# snes_visualization_combi.net
KiCad netlist of a schematic drawn in EAGLE
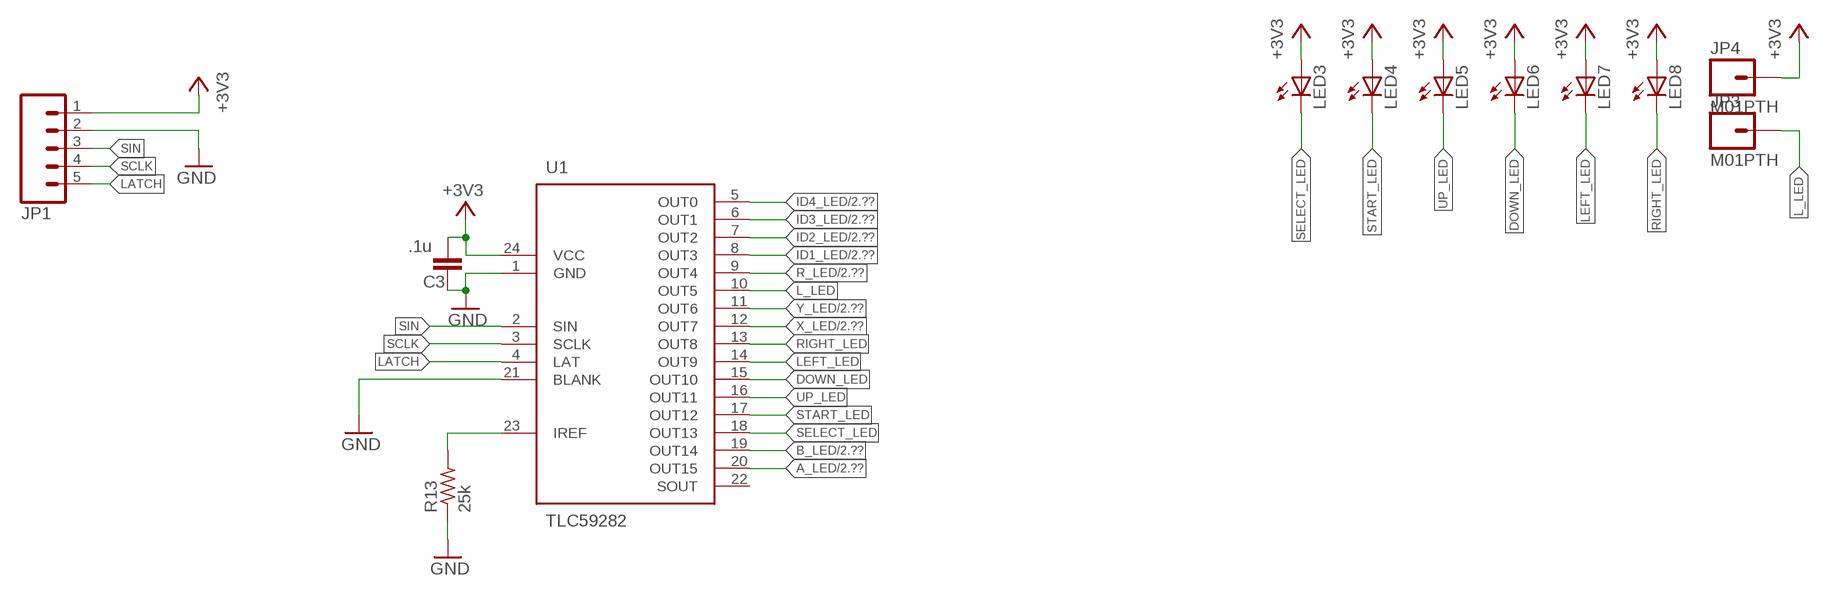
[diagram p0: schematic, sheet 1]
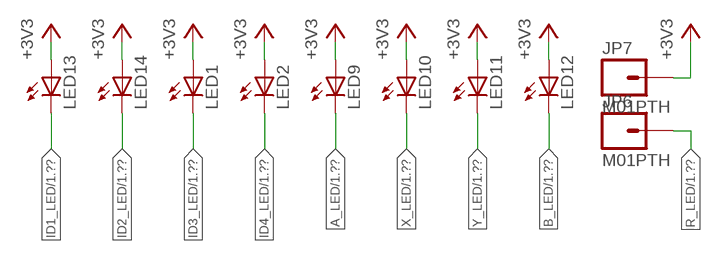
[diagram p1: schematic, sheet 2]

(export (version "E")
  (design (tool "Eeschema 10.0.6"))
  (components
    (comp (ref "JP6")
      (value "M01PTH")
      (footprint "eagle-import:1X01")
      (libsource (lib "eagle-import") (part "M01PTH"))
    )
    (comp (ref "JP7")
      (value "M01PTH")
      (footprint "eagle-import:1X01")
      (libsource (lib "eagle-import") (part "M01PTH"))
    )
    (comp (ref "LED1")
      (value "LED5MM")
      (footprint "eagle-import:LED5MM")
      (libsource (lib "eagle-import") (part "LED5MM"))
    )
    (comp (ref "LED2")
      (value "LED5MM")
      (footprint "eagle-import:LED5MM")
      (libsource (lib "eagle-import") (part "LED5MM"))
    )
    (comp (ref "LED9")
      (value "LED5MM")
      (footprint "eagle-import:LED5MM")
      (libsource (lib "eagle-import") (part "LED5MM"))
    )
    (comp (ref "LED10")
      (value "LED5MM")
      (footprint "eagle-import:LED5MM")
      (libsource (lib "eagle-import") (part "LED5MM"))
    )
    (comp (ref "LED11")
      (value "LED5MM")
      (footprint "eagle-import:LED5MM")
      (libsource (lib "eagle-import") (part "LED5MM"))
    )
    (comp (ref "LED12")
      (value "LED5MM")
      (footprint "eagle-import:LED5MM")
      (libsource (lib "eagle-import") (part "LED5MM"))
    )
    (comp (ref "LED13")
      (value "LED5MM")
      (footprint "eagle-import:LED5MM")
      (libsource (lib "eagle-import") (part "LED5MM"))
    )
    (comp (ref "LED14")
      (value "LED5MM")
      (footprint "eagle-import:LED5MM")
      (libsource (lib "eagle-import") (part "LED5MM"))
    )
    (comp (ref "C3")
      (value ".1u")
      (footprint "eagle-import:C0603")
      (libsource (lib "eagle-import") (part "C-EUC0603"))
    )
    (comp (ref "JP1")
      (value "M05PTH")
      (footprint "eagle-import:1X05")
      (libsource (lib "eagle-import") (part "M05PTH"))
    )
    (comp (ref "JP3")
      (value "M01PTH")
      (footprint "eagle-import:1X01")
      (libsource (lib "eagle-import") (part "M01PTH"))
    )
    (comp (ref "JP4")
      (value "M01PTH")
      (footprint "eagle-import:1X01")
      (libsource (lib "eagle-import") (part "M01PTH"))
    )
    (comp (ref "LED3")
      (value "LED3MM")
      (footprint "eagle-import:LED3MM")
      (libsource (lib "eagle-import") (part "LED3MM"))
    )
    (comp (ref "LED4")
      (value "LED3MM")
      (footprint "eagle-import:LED3MM")
      (libsource (lib "eagle-import") (part "LED3MM"))
    )
    (comp (ref "LED5")
      (value "LED5MM")
      (footprint "eagle-import:LED5MM")
      (libsource (lib "eagle-import") (part "LED5MM"))
    )
    (comp (ref "LED6")
      (value "LED5MM")
      (footprint "eagle-import:LED5MM")
      (libsource (lib "eagle-import") (part "LED5MM"))
    )
    (comp (ref "LED7")
      (value "LED5MM")
      (footprint "eagle-import:LED5MM")
      (libsource (lib "eagle-import") (part "LED5MM"))
    )
    (comp (ref "LED8")
      (value "LED5MM")
      (footprint "eagle-import:LED5MM")
      (libsource (lib "eagle-import") (part "LED5MM"))
    )
    (comp (ref "R13")
      (value "25k")
      (footprint "eagle-import:R0805")
      (libsource (lib "eagle-import") (part "R-US_R0805"))
    )
    (comp (ref "U1")
      (value "TLC59282")
      (footprint "eagle-import:R-PDSO-G24")
      (libsource (lib "eagle-import") (part "TLC59282"))
    )
  )
  (nets
    (net (code "1") (name "+3V3") (class "Default")
      (node (ref "C3") (pin "1") (pinfunction "1_1") (pintype "passive"))
      (node (ref "JP1") (pin "1") (pinfunction "1_1") (pintype "passive"))
      (node (ref "JP4") (pin "1") (pinfunction "1_1") (pintype "passive"))
      (node (ref "JP7") (pin "1") (pinfunction "1_1") (pintype "passive"))
      (node (ref "LED1") (pin "A") (pinfunction "A_A") (pintype "passive"))
      (node (ref "LED10") (pin "A") (pinfunction "A_A") (pintype "passive"))
      (node (ref "LED11") (pin "A") (pinfunction "A_A") (pintype "passive"))
      (node (ref "LED12") (pin "A") (pinfunction "A_A") (pintype "passive"))
      (node (ref "LED13") (pin "A") (pinfunction "A_A") (pintype "passive"))
      (node (ref "LED14") (pin "A") (pinfunction "A_A") (pintype "passive"))
      (node (ref "LED2") (pin "A") (pinfunction "A_A") (pintype "passive"))
      (node (ref "LED3") (pin "A") (pinfunction "A_A") (pintype "passive"))
      (node (ref "LED4") (pin "A") (pinfunction "A_A") (pintype "passive"))
      (node (ref "LED5") (pin "A") (pinfunction "A_A") (pintype "passive"))
      (node (ref "LED6") (pin "A") (pinfunction "A_A") (pintype "passive"))
      (node (ref "LED7") (pin "A") (pinfunction "A_A") (pintype "passive"))
      (node (ref "LED8") (pin "A") (pinfunction "A_A") (pintype "passive"))
      (node (ref "LED9") (pin "A") (pinfunction "A_A") (pintype "passive"))
      (node (ref "U1") (pin "24") (pinfunction "VCC_24") (pintype "input"))
    )
    (net (code "2") (name "A_LED") (class "Default")
      (node (ref "LED9") (pin "K") (pinfunction "C_K") (pintype "passive"))
      (node (ref "U1") (pin "20") (pinfunction "OUT15_20") (pintype "input"))
    )
    (net (code "3") (name "B_LED") (class "Default")
      (node (ref "LED12") (pin "K") (pinfunction "C_K") (pintype "passive"))
      (node (ref "U1") (pin "19") (pinfunction "OUT14_19") (pintype "input"))
    )
    (net (code "4") (name "DOWN_LED") (class "Default")
      (node (ref "LED6") (pin "K") (pinfunction "C_K") (pintype "passive"))
      (node (ref "U1") (pin "15") (pinfunction "OUT10_15") (pintype "input"))
    )
    (net (code "5") (name "GND") (class "Default")
      (node (ref "C3") (pin "2") (pinfunction "2_2") (pintype "passive"))
      (node (ref "JP1") (pin "2") (pinfunction "2_2") (pintype "passive"))
      (node (ref "R13") (pin "1") (pinfunction "1_1") (pintype "passive"))
      (node (ref "U1") (pin "1") (pinfunction "GND_1") (pintype "input"))
      (node (ref "U1") (pin "21") (pinfunction "BLANK_21") (pintype "input"))
    )
    (net (code "6") (name "ID1_LED") (class "Default")
      (node (ref "LED13") (pin "K") (pinfunction "C_K") (pintype "passive"))
      (node (ref "U1") (pin "8") (pinfunction "OUT3_8") (pintype "input"))
    )
    (net (code "7") (name "ID2_LED") (class "Default")
      (node (ref "LED14") (pin "K") (pinfunction "C_K") (pintype "passive"))
      (node (ref "U1") (pin "7") (pinfunction "OUT2_7") (pintype "input"))
    )
    (net (code "8") (name "ID3_LED") (class "Default")
      (node (ref "LED1") (pin "K") (pinfunction "C_K") (pintype "passive"))
      (node (ref "U1") (pin "6") (pinfunction "OUT1_6") (pintype "input"))
    )
    (net (code "9") (name "ID4_LED") (class "Default")
      (node (ref "LED2") (pin "K") (pinfunction "C_K") (pintype "passive"))
      (node (ref "U1") (pin "5") (pinfunction "OUT0_5") (pintype "input"))
    )
    (net (code "10") (name "LATCH") (class "Default")
      (node (ref "JP1") (pin "5") (pinfunction "5_5") (pintype "passive"))
      (node (ref "U1") (pin "4") (pinfunction "LAT_4") (pintype "input"))
    )
    (net (code "11") (name "LEFT_LED") (class "Default")
      (node (ref "LED7") (pin "K") (pinfunction "C_K") (pintype "passive"))
      (node (ref "U1") (pin "14") (pinfunction "OUT9_14") (pintype "input"))
    )
    (net (code "12") (name "L_LED") (class "Default")
      (node (ref "JP3") (pin "1") (pinfunction "1_1") (pintype "passive"))
      (node (ref "U1") (pin "10") (pinfunction "OUT5_10") (pintype "input"))
    )
    (net (code "13") (name "Net-(U1-IREF)") (class "Default")
      (node (ref "R13") (pin "2") (pinfunction "2_2") (pintype "passive"))
      (node (ref "U1") (pin "23") (pinfunction "IREF_23") (pintype "input"))
    )
    (net (code "14") (name "RIGHT_LED") (class "Default")
      (node (ref "LED8") (pin "K") (pinfunction "C_K") (pintype "passive"))
      (node (ref "U1") (pin "13") (pinfunction "OUT8_13") (pintype "input"))
    )
    (net (code "15") (name "R_LED") (class "Default")
      (node (ref "JP6") (pin "1") (pinfunction "1_1") (pintype "passive"))
      (node (ref "U1") (pin "9") (pinfunction "OUT4_9") (pintype "input"))
    )
    (net (code "16") (name "SCLK") (class "Default")
      (node (ref "JP1") (pin "4") (pinfunction "4_4") (pintype "passive"))
      (node (ref "U1") (pin "3") (pinfunction "SCLK_3") (pintype "input"))
    )
    (net (code "17") (name "SELECT_LED") (class "Default")
      (node (ref "LED3") (pin "K") (pinfunction "C_K") (pintype "passive"))
      (node (ref "U1") (pin "18") (pinfunction "OUT13_18") (pintype "input"))
    )
    (net (code "18") (name "SIN") (class "Default")
      (node (ref "JP1") (pin "3") (pinfunction "3_3") (pintype "passive"))
      (node (ref "U1") (pin "2") (pinfunction "SIN_2") (pintype "input"))
    )
    (net (code "19") (name "START_LED") (class "Default")
      (node (ref "LED4") (pin "K") (pinfunction "C_K") (pintype "passive"))
      (node (ref "U1") (pin "17") (pinfunction "OUT12_17") (pintype "input"))
    )
    (net (code "20") (name "UP_LED") (class "Default")
      (node (ref "LED5") (pin "K") (pinfunction "C_K") (pintype "passive"))
      (node (ref "U1") (pin "16") (pinfunction "OUT11_16") (pintype "input"))
    )
    (net (code "21") (name "X_LED") (class "Default")
      (node (ref "LED10") (pin "K") (pinfunction "C_K") (pintype "passive"))
      (node (ref "U1") (pin "12") (pinfunction "OUT7_12") (pintype "input"))
    )
    (net (code "22") (name "Y_LED") (class "Default")
      (node (ref "LED11") (pin "K") (pinfunction "C_K") (pintype "passive"))
      (node (ref "U1") (pin "11") (pinfunction "OUT6_11") (pintype "input"))
    )
    (net (code "23") (name "unconnected-(U1-SOUT-Pad22)") (class "Default")
      (node (ref "U1") (pin "22") (pinfunction "SOUT_22") (pintype "input"))
    )
  )
)
